# battery_18650_shield.net
KiCad netlist of a schematic drawn in EAGLE
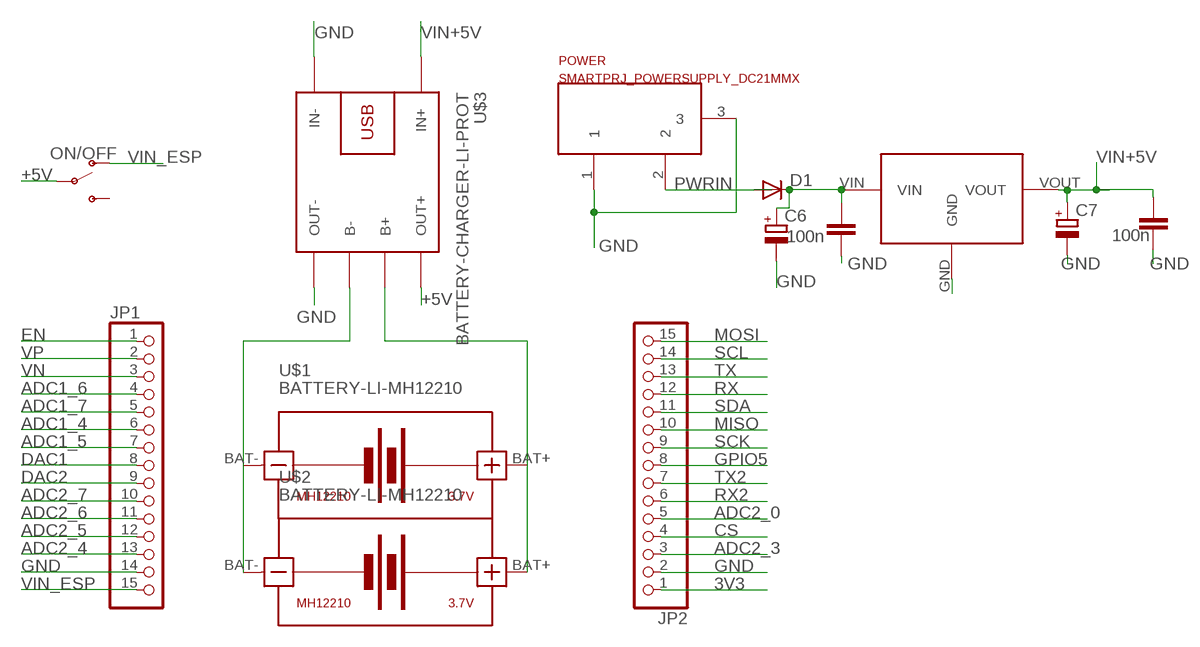
[diagram p0: schematic, sheet 1]

(export (version "E")
  (design (tool "Eeschema 10.0.6"))
  (components
    (comp (ref "C5")
      (value "100n")
      (footprint "eagle-import:C1206")
      (libsource (lib "eagle-import") (part "C-EUC1206"))
    )
    (comp (ref "C6")
      (value "CPOL-EUD")
      (footprint "eagle-import:PANASONIC_D")
      (libsource (lib "eagle-import") (part "CPOL-EUD"))
    )
    (comp (ref "C7")
      (value "CPOL-EUD")
      (footprint "eagle-import:PANASONIC_D")
      (libsource (lib "eagle-import") (part "CPOL-EUD"))
    )
    (comp (ref "C14")
      (value "100n")
      (footprint "eagle-import:C1206")
      (libsource (lib "eagle-import") (part "C-EUC1206"))
    )
    (comp (ref "D1")
      (value "DIODE-SMB")
      (footprint "eagle-import:SMB")
      (libsource (lib "eagle-import") (part "DIODE-SMB"))
    )
    (comp (ref "JP1")
      (value "PINHD-1X15")
      (footprint "eagle-import:1X15")
      (libsource (lib "eagle-import") (part "PINHD-1X15"))
    )
    (comp (ref "JP2")
      (value "PINHD-1X15")
      (footprint "eagle-import:1X15")
      (libsource (lib "eagle-import") (part "PINHD-1X15"))
    )
    (comp (ref "ON/OFF")
      (value "SWITCH-SPDT-PTH-11.6X4.0MM")
      (footprint "eagle-import:SWITCH_SPDT_PTH_11.6X4.0MM")
      (libsource (lib "eagle-import") (part "SWITCH-SPDT-PTH-11.6X4.0MM"))
    )
    (comp (ref "POWER")
      (value "SMARTPRJ_POWERSUPPLY_DC21MMX")
      (footprint "eagle-import:SMARTPRJ_POWERSUPPLY_DC-21MM")
      (libsource (lib "eagle-import") (part "SMARTPRJ_POWERSUPPLY_DC21MMX"))
    )
    (comp (ref "U$1")
      (value "BATTERY-LI-MH12210")
      (footprint "eagle-import:BATTERY-LI-MH12210")
      (libsource (lib "eagle-import") (part "BATTERY-LI-MH12210"))
    )
    (comp (ref "U$2")
      (value "BATTERY-LI-MH12210")
      (footprint "eagle-import:BATTERY-LI-MH12210")
      (libsource (lib "eagle-import") (part "BATTERY-LI-MH12210"))
    )
    (comp (ref "U$3")
      (value "BATTERY-CHARGER-LI-PROT")
      (footprint "eagle-import:BATTERY-CHARGER-LI-PROT")
      (libsource (lib "eagle-import") (part "BATTERY-CHARGER-LI-PROT"))
    )
    (comp (ref "U$5")
      (value "7805-TO263_7805")
      (footprint "eagle-import:7805-TO263_TO263")
      (libsource (lib "eagle-import") (part "7805-TO263_7805"))
    )
  )
  (nets
    (net (code "1") (name "/+5V") (class "Default")
      (node (ref "ON/OFF") (pin "2") (pinfunction "P_2") (pintype "passive"))
      (node (ref "U$3") (pin "OUT+") (pinfunction "OUT+_OUT+") (pintype "bidirectional"))
    )
    (net (code "2") (name "/3V3") (class "Default")
      (node (ref "JP2") (pin "1") (pinfunction "1_1") (pintype "passive"))
    )
    (net (code "3") (name "/ADC1_4") (class "Default")
      (node (ref "JP1") (pin "6") (pinfunction "6_6") (pintype "passive"))
    )
    (net (code "4") (name "/ADC1_5") (class "Default")
      (node (ref "JP1") (pin "7") (pinfunction "7_7") (pintype "passive"))
    )
    (net (code "5") (name "/ADC1_6") (class "Default")
      (node (ref "JP1") (pin "4") (pinfunction "4_4") (pintype "passive"))
    )
    (net (code "6") (name "/ADC1_7") (class "Default")
      (node (ref "JP1") (pin "5") (pinfunction "5_5") (pintype "passive"))
    )
    (net (code "7") (name "/ADC2_0") (class "Default")
      (node (ref "JP2") (pin "5") (pinfunction "5_5") (pintype "passive"))
    )
    (net (code "8") (name "/ADC2_3") (class "Default")
      (node (ref "JP2") (pin "3") (pinfunction "3_3") (pintype "passive"))
    )
    (net (code "9") (name "/ADC2_4") (class "Default")
      (node (ref "JP1") (pin "13") (pinfunction "13_13") (pintype "passive"))
    )
    (net (code "10") (name "/ADC2_5") (class "Default")
      (node (ref "JP1") (pin "12") (pinfunction "12_12") (pintype "passive"))
    )
    (net (code "11") (name "/ADC2_6") (class "Default")
      (node (ref "JP1") (pin "11") (pinfunction "11_11") (pintype "passive"))
    )
    (net (code "12") (name "/ADC2_7") (class "Default")
      (node (ref "JP1") (pin "10") (pinfunction "10_10") (pintype "passive"))
    )
    (net (code "13") (name "/CS") (class "Default")
      (node (ref "JP2") (pin "4") (pinfunction "4_4") (pintype "passive"))
    )
    (net (code "14") (name "/DAC1") (class "Default")
      (node (ref "JP1") (pin "8") (pinfunction "8_8") (pintype "passive"))
    )
    (net (code "15") (name "/DAC2") (class "Default")
      (node (ref "JP1") (pin "9") (pinfunction "9_9") (pintype "passive"))
    )
    (net (code "16") (name "/EN") (class "Default")
      (node (ref "JP1") (pin "1") (pinfunction "1_1") (pintype "passive"))
    )
    (net (code "17") (name "/GND") (class "Default")
      (node (ref "C14") (pin "1") (pinfunction "1_1") (pintype "passive"))
      (node (ref "C5") (pin "1") (pinfunction "1_1") (pintype "passive"))
      (node (ref "C6") (pin "-") (pinfunction "-_-") (pintype "passive"))
      (node (ref "C7") (pin "-") (pinfunction "-_-") (pintype "passive"))
      (node (ref "JP1") (pin "14") (pinfunction "14_14") (pintype "passive"))
      (node (ref "JP2") (pin "2") (pinfunction "2_2") (pintype "passive"))
      (node (ref "POWER") (pin "1") (pinfunction "1_1") (pintype "power_in"))
      (node (ref "POWER") (pin "3") (pinfunction "3_3") (pintype "power_in"))
      (node (ref "U$3") (pin "IN-") (pinfunction "IN-_IN-") (pintype "bidirectional"))
      (node (ref "U$3") (pin "OUT-") (pinfunction "OUT-_OUT-") (pintype "bidirectional"))
      (node (ref "U$5") (pin "GND") (pinfunction "GND_GND") (pintype "bidirectional"))
    )
    (net (code "18") (name "/GPIO5") (class "Default")
      (node (ref "JP2") (pin "8") (pinfunction "8_8") (pintype "passive"))
    )
    (net (code "19") (name "/MISO") (class "Default")
      (node (ref "JP2") (pin "10") (pinfunction "10_10") (pintype "passive"))
    )
    (net (code "20") (name "/MOSI") (class "Default")
      (node (ref "JP2") (pin "15") (pinfunction "15_15") (pintype "passive"))
    )
    (net (code "21") (name "/PWRIN") (class "Default")
      (node (ref "D1") (pin "A") (pinfunction "A_A") (pintype "passive"))
      (node (ref "POWER") (pin "2") (pinfunction "2_2") (pintype "power_in"))
    )
    (net (code "22") (name "/RX") (class "Default")
      (node (ref "JP2") (pin "12") (pinfunction "12_12") (pintype "passive"))
    )
    (net (code "23") (name "/RX2") (class "Default")
      (node (ref "JP2") (pin "6") (pinfunction "6_6") (pintype "passive"))
    )
    (net (code "24") (name "/SCK") (class "Default")
      (node (ref "JP2") (pin "9") (pinfunction "9_9") (pintype "passive"))
    )
    (net (code "25") (name "/SCL") (class "Default")
      (node (ref "JP2") (pin "14") (pinfunction "14_14") (pintype "passive"))
    )
    (net (code "26") (name "/SDA") (class "Default")
      (node (ref "JP2") (pin "11") (pinfunction "11_11") (pintype "passive"))
    )
    (net (code "27") (name "/TX") (class "Default")
      (node (ref "JP2") (pin "13") (pinfunction "13_13") (pintype "passive"))
    )
    (net (code "28") (name "/TX2") (class "Default")
      (node (ref "JP2") (pin "7") (pinfunction "7_7") (pintype "passive"))
    )
    (net (code "29") (name "/VIN+5V") (class "Default")
      (node (ref "C14") (pin "2") (pinfunction "2_2") (pintype "passive"))
      (node (ref "C7") (pin "+") (pinfunction "+_+") (pintype "passive"))
      (node (ref "U$3") (pin "IN+") (pinfunction "IN+_IN+") (pintype "bidirectional"))
      (node (ref "U$5") (pin "VOUT") (pinfunction "VOUT_VOUT") (pintype "bidirectional"))
    )
    (net (code "30") (name "/VIN_ESP") (class "Default")
      (node (ref "JP1") (pin "15") (pinfunction "15_15") (pintype "passive"))
      (node (ref "ON/OFF") (pin "1") (pinfunction "O_1") (pintype "passive"))
    )
    (net (code "31") (name "/VN") (class "Default")
      (node (ref "JP1") (pin "3") (pinfunction "3_3") (pintype "passive"))
    )
    (net (code "32") (name "/VP") (class "Default")
      (node (ref "JP1") (pin "2") (pinfunction "2_2") (pintype "passive"))
    )
    (net (code "33") (name "Net-(C5-Pad2)") (class "Default")
      (node (ref "C5") (pin "2") (pinfunction "2_2") (pintype "passive"))
      (node (ref "C6") (pin "+") (pinfunction "+_+") (pintype "passive"))
      (node (ref "D1") (pin "C") (pinfunction "C_C") (pintype "passive"))
      (node (ref "U$5") (pin "VIN") (pinfunction "VIN_VIN") (pintype "bidirectional"))
    )
    (net (code "34") (name "Net-(U$1-PadBAT+)") (class "Default")
      (node (ref "U$1") (pin "BAT+") (pinfunction "BAT+_BAT+") (pintype "power_in"))
      (node (ref "U$2") (pin "BAT+") (pinfunction "BAT+_BAT+") (pintype "power_in"))
      (node (ref "U$3") (pin "B+") (pinfunction "B+_B+") (pintype "bidirectional"))
    )
    (net (code "35") (name "Net-(U$1-PadBAT-)") (class "Default")
      (node (ref "U$1") (pin "BAT-") (pinfunction "BAT-_BAT-") (pintype "power_in"))
      (node (ref "U$2") (pin "BAT-") (pinfunction "BAT-_BAT-") (pintype "power_in"))
      (node (ref "U$3") (pin "B-") (pinfunction "B-_B-") (pintype "bidirectional"))
    )
    (net (code "36") (name "unconnected-(ON/OFF-S-Pad3)") (class "Default")
      (node (ref "ON/OFF") (pin "3") (pinfunction "S_3") (pintype "passive"))
    )
  )
)
